# Sheet1.net
KiCad netlist of a schematic drawn in Altium Designer
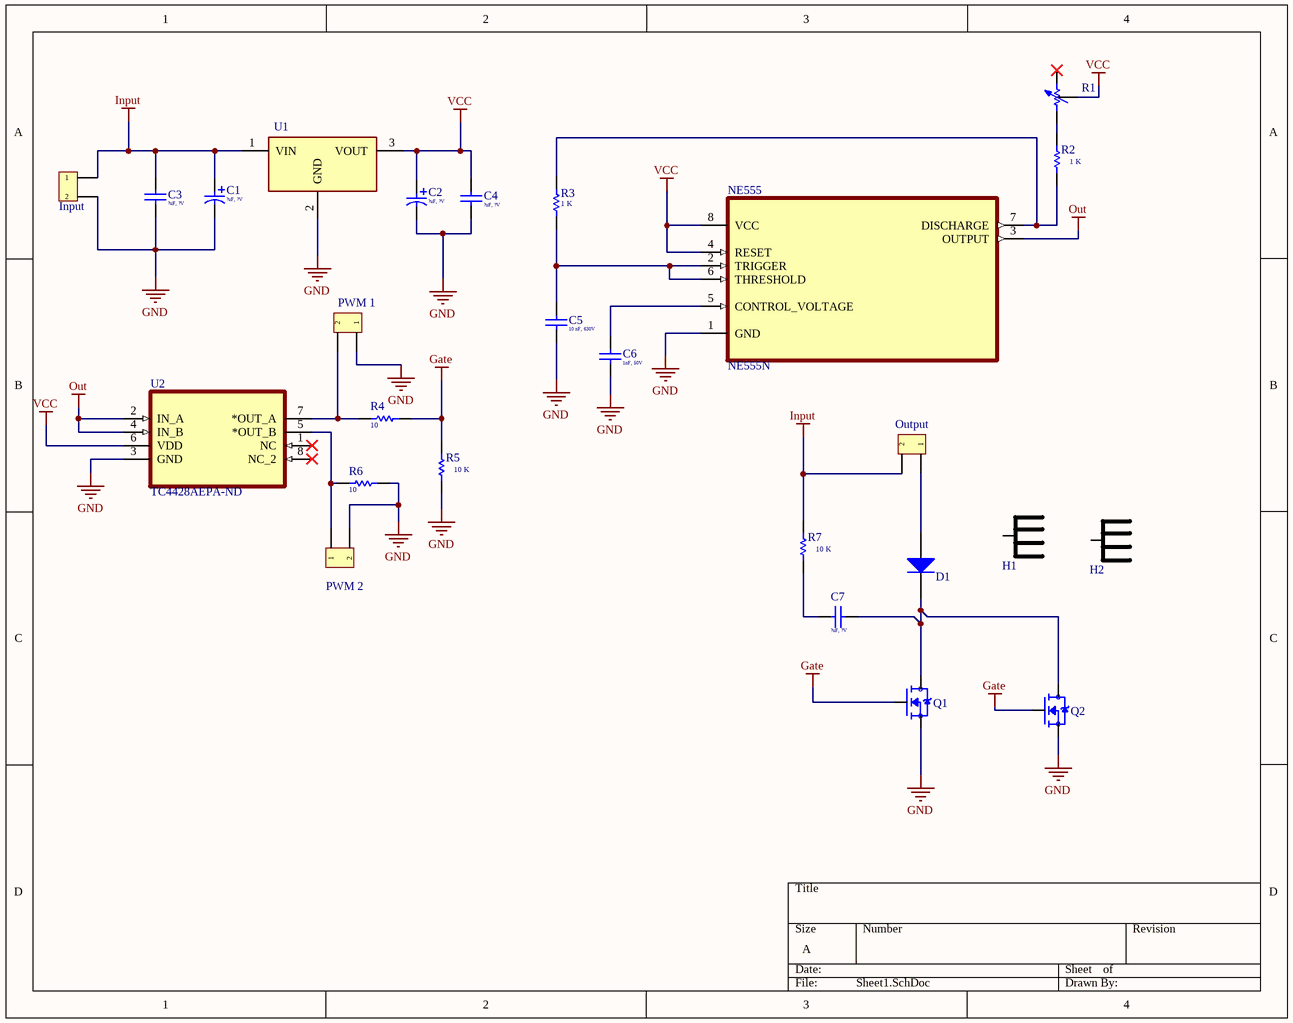
[diagram p0: Sheet1.SchDoc]

(export (version "E")
  (design (tool "Eeschema 10.0.6"))
  (components
    (comp (ref "C1")
      (value "?uF, ?V")
      (footprint "Capacitor Aluminum Electrolytic DIP 10*13*5")
      (description "Aluminum Electrolytic Capacitors")
      (fields (field (name "MF") "Nichicon") (field (name "MP") "UVR2A471MHD"))
      (libsource (lib "M_Derogarian Altium Library") (part "Capacitors Electrolytic"))
    )
    (comp (ref "C2")
      (value "?uF, ?V")
      (footprint "Capacitor Aluminum Electrolytic DIP 10*13*5")
      (description "Aluminum Electrolytic Capacitors")
      (fields (field (name "MF") "Nichicon") (field (name "MP") "UVR2A471MHD"))
      (libsource (lib "M_Derogarian Altium Library") (part "Capacitors Electrolytic"))
    )
    (comp (ref "C3")
      (value "?uF, ?V")
      (footprint "Capacitor Film DIP 01")
      (description "Ceramic & Polyester Capacitor")
      (fields (field (name "Comment") "(DIGIKEY Part Number)"))
      (libsource (lib "M_Derogarian Altium Library") (part "Capacitors Non-Electrolytic"))
    )
    (comp (ref "C4")
      (value "?uF, ?V")
      (footprint "Capacitor Film DIP 01")
      (description "Ceramic & Polyester Capacitor")
      (fields (field (name "Comment") "(DIGIKEY Part Number)"))
      (libsource (lib "M_Derogarian Altium Library") (part "Capacitors Non-Electrolytic"))
    )
    (comp (ref "C5")
      (value "10 nF, 630V")
      (footprint "Capacitor Film DIP 01")
      (description "Ceramic & Polyester Capacitor")
      (fields (field (name "Comment") "(DIGIKEY Part Number)"))
      (libsource (lib "M_Derogarian Altium Library") (part "Capacitors Non-Electrolytic"))
    )
    (comp (ref "C6")
      (value "1nF, 50V")
      (footprint "Capacitor Film DIP 01")
      (description "Ceramic & Polyester Capacitor")
      (fields (field (name "Comment") "(DIGIKEY Part Number)"))
      (libsource (lib "M_Derogarian Altium Library") (part "Capacitors Non-Electrolytic"))
    )
    (comp (ref "C7")
      (value "?uF, ?V")
      (footprint "Capacitor Ceramic Lens DIP")
      (description "Ceramic & Polyester Capacitor")
      (fields (field (name "Comment") "(DIGIKEY Part Number)"))
      (libsource (lib "M_Derogarian Altium Library") (part "Capacitors Non-Electrolytic"))
    )
    (comp (ref "D1")
      (value "(DIGIKEY Part Number)")
      (footprint "Diode DIP DO-41 01")
      (description "Through Hole & SMD Diode")
      (fields (field (name "PUBLISHER") "Altium Limited"))
      (libsource (lib "M_Derogarian Altium Library") (part "Diode"))
    )
    (comp (ref "H1")
      (value "(DIGIKEY Part Number)")
      (footprint "HEATSINK 02")
      (description "Heat Sink TO-220 Aluminum 20.0W @ 60Â°C Board Level, Vertical")
      (fields (field (name "MP") "530002B02500G") (field (name "MF") "Aavid Thermalloy"))
      (libsource (lib "M_Derogarian Altium Library") (part "Heat Sink"))
    )
    (comp (ref "H2")
      (value "(DIGIKEY Part Number)")
      (footprint "HEATSINK 05")
      (description "Heat Sink TO-220 Aluminum 20.0W @ 60Â°C Board Level, Vertical")
      (fields (field (name "MP") "530002B02500G") (field (name "MF") "Aavid Thermalloy"))
      (libsource (lib "M_Derogarian Altium Library") (part "Heat Sink"))
    )
    (comp (ref "Input")
      (value "(DIGIKEY Part Number)")
      (footprint "Phoenix Contact 2x2 Male Straight")
      (description "Contact-Phoenix 2x")
      (fields
        (field (name "MANUFACTURER") "Phoenix Contact")
        (field (name "MANUFACTURER PART NUMBER") "1715721")
      )
      (libsource (lib "M_Derogarian Altium Library") (part "Contact-Phoenix 2x"))
    )
    (comp (ref "NE555")
      (value "NE555N")
      (footprint "NE555 DIP-8")
      (description "555 Type, Timer/Oscillator (Single) IC 500kHz 8-DIP")
      (fields (field (name "MF") "STMicroelectronics"))
      (libsource (lib "M_Derogarian Altium Library") (part "NE555N"))
    )
    (comp (ref "Output")
      (value "(DIGIKEY Part Number)")
      (footprint "Phoenix Contact 2x2 Male Straight")
      (description "Contact-Phoenix 2x")
      (fields
        (field (name "MANUFACTURER") "Phoenix Contact")
        (field (name "MANUFACTURER PART NUMBER") "1715721")
      )
      (libsource (lib "") (part "Contact-Phoenix 2x_1"))
    )
    (comp (ref "PWM 1")
      (value "(DIGIKEY Part Number)")
      (footprint "Header 01 1x2")
      (description "Contact-Phoenix 2x")
      (fields
        (field (name "MANUFACTURER") "Phoenix Contact")
        (field (name "MANUFACTURER PART NUMBER") "1715721")
      )
      (libsource (lib "") (part "Contact-Phoenix 2x_1"))
    )
    (comp (ref "PWM 2")
      (value "(DIGIKEY Part Number)")
      (footprint "Header 01 1x2")
      (description "Contact-Phoenix 2x")
      (fields
        (field (name "MANUFACTURER") "Phoenix Contact")
        (field (name "MANUFACTURER PART NUMBER") "1715721")
      )
      (libsource (lib "") (part "Contact-Phoenix 2x_2"))
    )
    (comp (ref "Q1")
      (value "(DIGIKEY Part Number)")
      (footprint "MOSFET DIP TO-220")
      (description "N-Channel MOSFET")
      (fields (field (name "MP") "FDN360P") (field (name "MF") "ON Semiconductor"))
      (libsource (lib "M_Derogarian Altium Library") (part "Transistor MOSFET"))
    )
    (comp (ref "Q2")
      (value "(DIGIKEY Part Number)")
      (footprint "MOSFET DIP TO-220")
      (description "N-Channel MOSFET")
      (fields (field (name "MP") "FDN360P") (field (name "MF") "ON Semiconductor"))
      (libsource (lib "M_Derogarian Altium Library") (part "Transistor MOSFET"))
    )
    (comp (ref "R1")
      (value "(DIGIKEY Part Number)")
      (footprint "Resistor Variable DIP 03")
      (description "Trimmer Potentiometer Cermet Top Adjustment")
      (fields (field (name "PUBLISHER") "Altium Limited"))
      (libsource (lib "M_Derogarian Altium Library") (part "Resistor Variable"))
    )
    (comp (ref "R2")
      (value "1 K")
      (footprint "Resistor DIP 0.25W 01")
      (description "Through Hole & SMD")
      (fields (field (name "Comment") "(DIGIKEY Part Number)") (field (name "PUBLISHER") "Altium Limited"))
      (libsource (lib "M_Derogarian Altium Library") (part "Resistor"))
    )
    (comp (ref "R3")
      (value "1 K")
      (footprint "Resistor DIP 0.25W 01")
      (description "Through Hole & SMD")
      (fields (field (name "Comment") "(DIGIKEY Part Number)") (field (name "PUBLISHER") "Altium Limited"))
      (libsource (lib "M_Derogarian Altium Library") (part "Resistor"))
    )
    (comp (ref "R4")
      (value "10")
      (footprint "Resistor DIP 0.25W 01")
      (description "Through Hole & SMD")
      (fields (field (name "Comment") "(DIGIKEY Part Number)") (field (name "PUBLISHER") "Altium Limited"))
      (libsource (lib "M_Derogarian Altium Library") (part "Resistor"))
    )
    (comp (ref "R5")
      (value "10 K")
      (footprint "Resistor DIP 0.25W 01")
      (description "Through Hole & SMD")
      (fields (field (name "Comment") "(DIGIKEY Part Number)") (field (name "PUBLISHER") "Altium Limited"))
      (libsource (lib "M_Derogarian Altium Library") (part "Resistor"))
    )
    (comp (ref "R6")
      (value "10")
      (footprint "Resistor DIP 0.25W 01")
      (description "Through Hole & SMD")
      (fields (field (name "Comment") "(DIGIKEY Part Number)") (field (name "PUBLISHER") "Altium Limited"))
      (libsource (lib "M_Derogarian Altium Library") (part "Resistor"))
    )
    (comp (ref "R7")
      (value "10 K")
      (footprint "Resistor DIP 0.25W 01")
      (description "Through Hole & SMD")
      (fields (field (name "Comment") "(DIGIKEY Part Number)") (field (name "PUBLISHER") "Altium Limited"))
      (libsource (lib "M_Derogarian Altium Library") (part "Resistor"))
    )
    (comp (ref "U1")
      (value "(DIGIKEY Part Number)")
      (footprint "Linear Regulator DIP TO-220-3")
      (description "Voltage Regulators - Linear, Low Drop Out (LDO) Regulators")
      (fields
        (field (name "MANUFACTURER") "STMicroelectronics")
        (field (name "MANUFACTURER PART NUMBER") "LD1117DT33")
      )
      (libsource (lib "M_Derogarian Altium Library") (part "Linear Regulator"))
    )
    (comp (ref "U2")
      (value "TC4428AEPA-ND")
      (footprint "Gate Driver TC4428AEPA DIP 01")
      (description "Low-Side Gate Driver IC Inverting, Non-Inverting 8-PDIP")
      (fields (field (name "DIGI-KEY_PART_NUMBER") "TC4428CPA-ND") (field (name "MP") "TC4428CPA"))
      (libsource (lib "M_Derogarian Altium Library") (part "Gate Driver TC4428CPA"))
    )
  )
  (nets
    (net (code "1") (name "GND") (class "Default")
      (node (ref "C1") (pin "2") (pinfunction "2_2") (pintype "passive"))
      (node (ref "C2") (pin "2") (pinfunction "2_2") (pintype "passive"))
      (node (ref "C3") (pin "1") (pinfunction "1_1") (pintype "passive"))
      (node (ref "C4") (pin "1") (pinfunction "1_1") (pintype "passive"))
      (node (ref "C5") (pin "1") (pinfunction "1_1") (pintype "passive"))
      (node (ref "C6") (pin "1") (pinfunction "1_1") (pintype "passive"))
      (node (ref "Input") (pin "2") (pinfunction "2_2") (pintype "power_in"))
      (node (ref "NE555") (pin "1") (pinfunction "GND_1") (pintype "passive"))
      (node (ref "PWM 1") (pin "1") (pinfunction "1_1") (pintype "power_in"))
      (node (ref "PWM 2") (pin "2") (pinfunction "2_2") (pintype "power_in"))
      (node (ref "Q1") (pin "3") (pinfunction "S_3") (pintype "passive"))
      (node (ref "Q2") (pin "3") (pinfunction "S_3") (pintype "passive"))
      (node (ref "R5") (pin "2") (pinfunction "2_2") (pintype "passive"))
      (node (ref "R6") (pin "2") (pinfunction "2_2") (pintype "passive"))
      (node (ref "U1") (pin "2") (pinfunction "GND_2") (pintype "power_in"))
      (node (ref "U2") (pin "3") (pinfunction "GND_3") (pintype "passive"))
    )
    (net (code "2") (name "Gate") (class "Default")
      (node (ref "Q1") (pin "1") (pinfunction "G_1") (pintype "passive"))
      (node (ref "Q2") (pin "1") (pinfunction "G_1") (pintype "passive"))
      (node (ref "R4") (pin "2") (pinfunction "2_2") (pintype "passive"))
      (node (ref "R5") (pin "1") (pinfunction "1_1") (pintype "passive"))
    )
    (net (code "3") (name "Input") (class "Default")
      (node (ref "C1") (pin "1") (pinfunction "1_1") (pintype "passive"))
      (node (ref "C3") (pin "2") (pinfunction "2_2") (pintype "passive"))
      (node (ref "Input") (pin "1") (pinfunction "1_1") (pintype "power_in"))
      (node (ref "Output") (pin "2") (pinfunction "2_2") (pintype "power_in"))
      (node (ref "R7") (pin "1") (pinfunction "1_1") (pintype "passive"))
      (node (ref "U1") (pin "1") (pinfunction "VIN_1") (pintype "power_in"))
    )
    (net (code "4") (name "Net-(C7-Pad1)") (class "Default")
      (node (ref "C7") (pin "1") (pinfunction "1_1") (pintype "passive"))
      (node (ref "R7") (pin "2") (pinfunction "2_2") (pintype "passive"))
    )
    (net (code "5") (name "Net-(D1-A)") (class "Default")
      (node (ref "D1") (pin "1") (pinfunction "A_1") (pintype "passive"))
      (node (ref "Output") (pin "1") (pinfunction "1_1") (pintype "power_in"))
    )
    (net (code "6") (name "Net-(D1-K)") (class "Default")
      (node (ref "C7") (pin "2") (pinfunction "2_2") (pintype "passive"))
      (node (ref "D1") (pin "2") (pinfunction "K_2") (pintype "passive"))
      (node (ref "Q1") (pin "2") (pinfunction "D_2") (pintype "passive"))
      (node (ref "Q2") (pin "2") (pinfunction "D_2") (pintype "passive"))
    )
    (net (code "7") (name "Net-(NE555-CONTROL_VOLTAGE)") (class "Default")
      (node (ref "C6") (pin "2") (pinfunction "2_2") (pintype "passive"))
      (node (ref "NE555") (pin "5") (pinfunction "CONTROL_VOLTAGE_5") (pintype "input"))
    )
    (net (code "8") (name "Net-(NE555-DISCHARGE)") (class "Default")
      (node (ref "NE555") (pin "7") (pinfunction "DISCHARGE_7") (pintype "output"))
      (node (ref "R2") (pin "2") (pinfunction "2_2") (pintype "passive"))
      (node (ref "R3") (pin "2") (pinfunction "2_2") (pintype "passive"))
    )
    (net (code "9") (name "Net-(NE555-THRESHOLD)") (class "Default")
      (node (ref "C5") (pin "2") (pinfunction "2_2") (pintype "passive"))
      (node (ref "NE555") (pin "2") (pinfunction "TRIGGER_2") (pintype "input"))
      (node (ref "NE555") (pin "6") (pinfunction "THRESHOLD_6") (pintype "input"))
      (node (ref "R3") (pin "1") (pinfunction "1_1") (pintype "passive"))
    )
    (net (code "10") (name "Net-(R1-Pad1)") (class "Default")
      (node (ref "R1") (pin "1") (pinfunction "1_1") (pintype "passive"))
      (node (ref "R2") (pin "1") (pinfunction "1_1") (pintype "passive"))
    )
    (net (code "11") (name "Net-(U2-*OUT_A)") (class "Default")
      (node (ref "PWM 1") (pin "2") (pinfunction "2_2") (pintype "power_in"))
      (node (ref "R4") (pin "1") (pinfunction "1_1") (pintype "passive"))
      (node (ref "U2") (pin "7") (pinfunction "*OUT_A_7") (pintype "passive"))
    )
    (net (code "12") (name "Net-(U2-*OUT_B)") (class "Default")
      (node (ref "PWM 2") (pin "1") (pinfunction "1_1") (pintype "power_in"))
      (node (ref "R6") (pin "1") (pinfunction "1_1") (pintype "passive"))
      (node (ref "U2") (pin "5") (pinfunction "*OUT_B_5") (pintype "passive"))
    )
    (net (code "13") (name "Out") (class "Default")
      (node (ref "NE555") (pin "3") (pinfunction "OUTPUT_3") (pintype "output"))
      (node (ref "U2") (pin "2") (pinfunction "IN_A_2") (pintype "input"))
      (node (ref "U2") (pin "4") (pinfunction "IN_B_4") (pintype "input"))
    )
    (net (code "14") (name "VCC") (class "Default")
      (node (ref "C2") (pin "1") (pinfunction "1_1") (pintype "passive"))
      (node (ref "C4") (pin "2") (pinfunction "2_2") (pintype "passive"))
      (node (ref "NE555") (pin "4") (pinfunction "RESET_4") (pintype "input"))
      (node (ref "NE555") (pin "8") (pinfunction "VCC_8") (pintype "power_in"))
      (node (ref "R1") (pin "2") (pinfunction "2_2") (pintype "passive"))
      (node (ref "U1") (pin "3") (pinfunction "VOUT_3") (pintype "power_in"))
      (node (ref "U2") (pin "6") (pinfunction "VDD_6") (pintype "power_in"))
    )
    (net (code "15") (name "unconnected-(R1-Pad3)") (class "Default")
      (node (ref "R1") (pin "3") (pinfunction "3_3") (pintype "passive+no_connect"))
    )
    (net (code "16") (name "unconnected-(U2-NC-Pad1)") (class "Default")
      (node (ref "U2") (pin "1") (pinfunction "NC_1") (pintype "input+no_connect"))
    )
    (net (code "17") (name "unconnected-(U2-NC_2-Pad8)") (class "Default")
      (node (ref "U2") (pin "8") (pinfunction "NC_2_8") (pintype "input+no_connect"))
    )
  )
)
